# EC25.net
KiCad netlist of a schematic drawn in Altium Designer
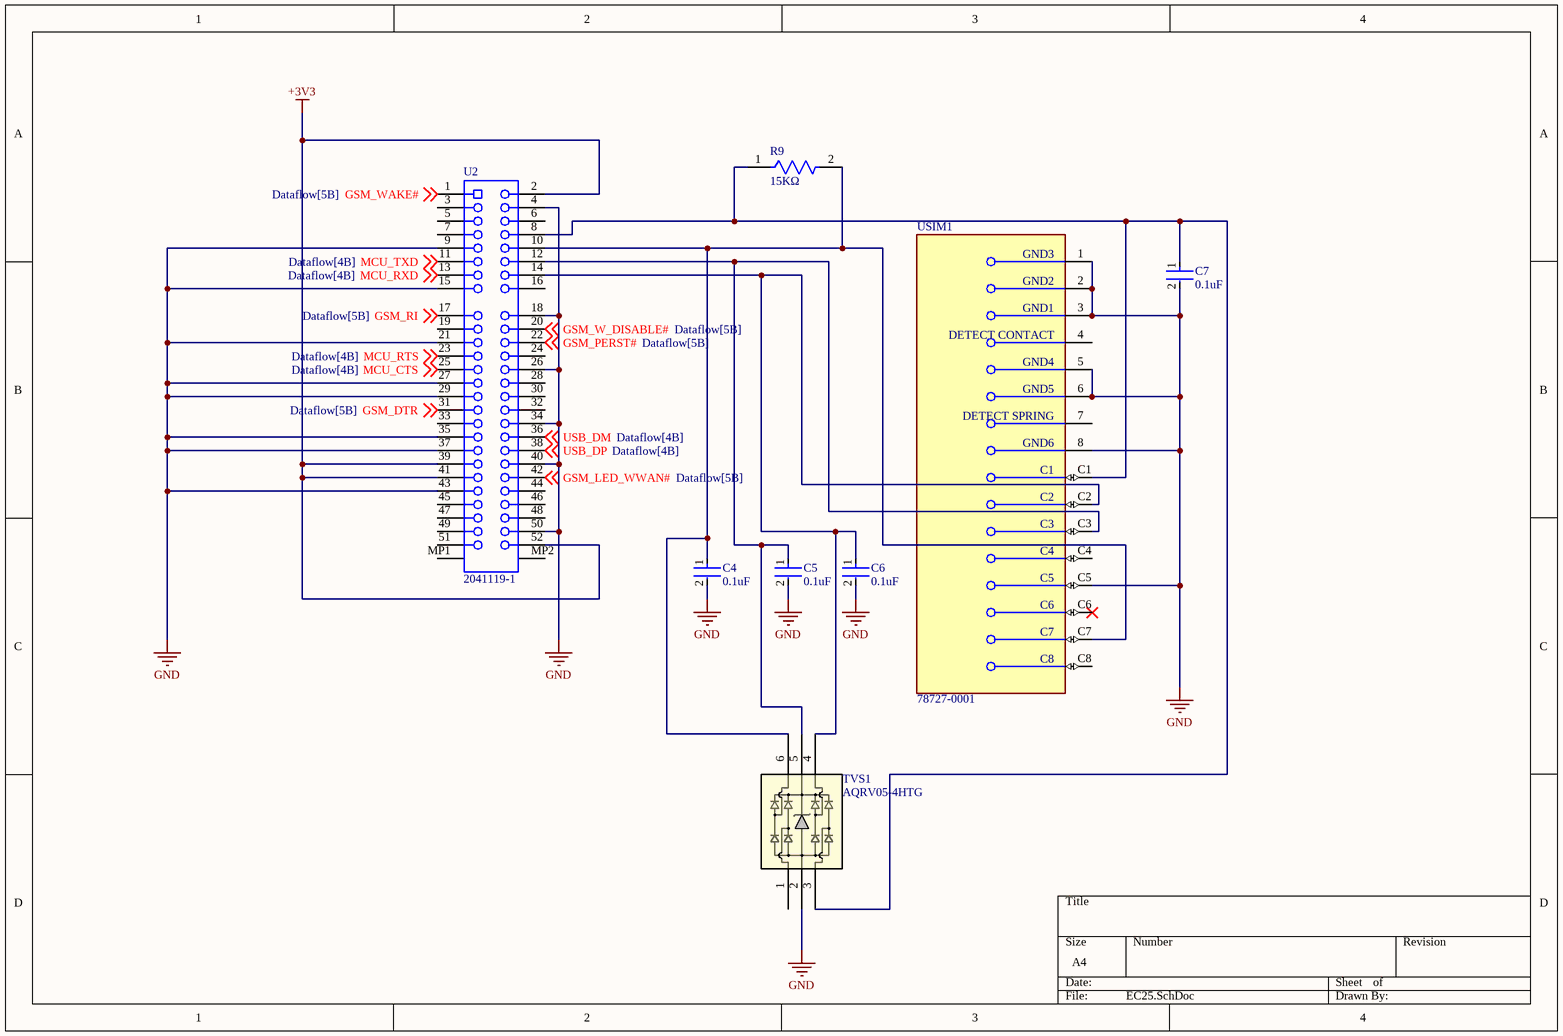
[diagram p0: EC25.SchDoc]

(export (version "E")
  (design (tool "Eeschema 10.0.6"))
  (components
    (comp (ref "C4")
      (value "0.1uF")
      (footprint "FP-C0603C-CF-MFG")
      (description "C0603C104J5RACTU CAP CER 0.1UF 50V 5% X7R 0603")
      (fields (field (name "TOLERANCE") "0.05") (field (name "MANUFACTURER PART NUMBER") "C0603C104J5RACTU"))
      (libsource (lib "Altium Content Vault") (part "b4654b650e69147ec39a6b967a45e02"))
    )
    (comp (ref "C5")
      (value "0.1uF")
      (footprint "FP-C0603C-CF-MFG")
      (description "C0603C104J5RACTU CAP CER 0.1UF 50V 5% X7R 0603")
      (fields (field (name "TOLERANCE") "0.05") (field (name "MANUFACTURER PART NUMBER") "C0603C104J5RACTU"))
      (libsource (lib "Altium Content Vault") (part "b4654b650e69147ec39a6b967a45e02"))
    )
    (comp (ref "C6")
      (value "0.1uF")
      (footprint "FP-C0603C-CF-MFG")
      (description "C0603C104J5RACTU CAP CER 0.1UF 50V 5% X7R 0603")
      (fields (field (name "TOLERANCE") "0.05") (field (name "MANUFACTURER PART NUMBER") "C0603C104J5RACTU"))
      (libsource (lib "Altium Content Vault") (part "b4654b650e69147ec39a6b967a45e02"))
    )
    (comp (ref "C7")
      (value "0.1uF")
      (footprint "FP-C0603C-CF-MFG")
      (description "C0603C104J5RACTU CAP CER 0.1UF 50V 5% X7R 0603")
      (fields (field (name "TOLERANCE") "0.05") (field (name "MANUFACTURER PART NUMBER") "C0603C104J5RACTU"))
      (libsource (lib "Altium Content Vault") (part "b4654b650e69147ec39a6b967a45e02"))
    )
    (comp (ref "R9")
      (value "15KΩ")
      (footprint "FP-CRGP2512-IPC_C")
      (description "CRGP2512F15K CRGP2512 15KΩ 2W ±100ppm/°C 1% 500V")
      (fields (field (name "TOLERANCE") "0.01") (field (name "MANUFACTURER PART NUMBER") "CRGP2512F15K"))
      (libsource (lib "Altium Content Vault") (part "1029c3af85768c4190bb7ad29bc67b5"))
    )
    (comp (ref "TVS1")
      (value "AQRV05-4HTG")
      (footprint "SOT23-6_LTF")
      (description "No Description Available")
      (libsource (lib "AQRV05-4HTG") (part "AQRV05-4HTG"))
    )
    (comp (ref "U2")
      (value "2041119-1")
      (footprint "TECO-2041119-1_3_V")
      (fields (field (name "MANUFACTURER") "TE Connectivity"))
      (libsource (lib "Altium Content Vault") (part "CN-2P-2F-R52"))
    )
    (comp (ref "USIM1")
      (value "78727-0001")
      (footprint "FP-78727-0001-MFG")
      (description "CONN MICRO SIM CARD PUSH-PULL")
      (fields
        (field (name "OCTOPART") "https://octopart.com/78727-0001-molex-24436211")
        (field (name "MANUFACTURER") "Molex")
      )
      (libsource (lib "Altium Content Vault") (part "009f4dc804d36d98447081ee26a76dc"))
    )
  )
  (nets
    (net (code "1") (name "+3V3") (class "Default")
      (node (ref "U2") (pin "2") (pinfunction "2_2") (pintype "passive"))
      (node (ref "U2") (pin "39") (pinfunction "39_39") (pintype "passive"))
      (node (ref "U2") (pin "41") (pinfunction "41_41") (pintype "passive"))
      (node (ref "U2") (pin "52") (pinfunction "52_52") (pintype "passive"))
    )
    (net (code "2") (name "GND") (class "Default")
      (node (ref "C4") (pin "2") (pinfunction "2_2") (pintype "passive"))
      (node (ref "C5") (pin "2") (pinfunction "2_2") (pintype "passive"))
      (node (ref "C6") (pin "2") (pinfunction "2_2") (pintype "passive"))
      (node (ref "C7") (pin "2") (pinfunction "2_2") (pintype "passive"))
      (node (ref "TVS1") (pin "2") (pinfunction "2_2") (pintype "passive"))
      (node (ref "U2") (pin "15") (pinfunction "15_15") (pintype "passive"))
      (node (ref "U2") (pin "18") (pinfunction "18_18") (pintype "passive"))
      (node (ref "U2") (pin "21") (pinfunction "21_21") (pintype "passive"))
      (node (ref "U2") (pin "26") (pinfunction "26_26") (pintype "passive"))
      (node (ref "U2") (pin "27") (pinfunction "27_27") (pintype "passive"))
      (node (ref "U2") (pin "29") (pinfunction "29_29") (pintype "passive"))
      (node (ref "U2") (pin "34") (pinfunction "34_34") (pintype "passive"))
      (node (ref "U2") (pin "35") (pinfunction "35_35") (pintype "passive"))
      (node (ref "U2") (pin "37") (pinfunction "37_37") (pintype "passive"))
      (node (ref "U2") (pin "4") (pinfunction "4_4") (pintype "passive"))
      (node (ref "U2") (pin "40") (pinfunction "40_40") (pintype "passive"))
      (node (ref "U2") (pin "43") (pinfunction "43_43") (pintype "passive"))
      (node (ref "U2") (pin "50") (pinfunction "50_50") (pintype "passive"))
      (node (ref "U2") (pin "9") (pinfunction "9_9") (pintype "passive"))
      (node (ref "USIM1") (pin "1") (pinfunction "GND3_1") (pintype "power_in"))
      (node (ref "USIM1") (pin "2") (pinfunction "GND2_2") (pintype "power_in"))
      (node (ref "USIM1") (pin "3") (pinfunction "GND1_3") (pintype "power_in"))
      (node (ref "USIM1") (pin "5") (pinfunction "GND4_5") (pintype "power_in"))
      (node (ref "USIM1") (pin "6") (pinfunction "GND5_6") (pintype "power_in"))
      (node (ref "USIM1") (pin "8") (pinfunction "GND6_8") (pintype "power_in"))
      (node (ref "USIM1") (pin "C5") (pinfunction "C5_C5") (pintype "bidirectional"))
    )
    (net (code "3") (name "GSM_DTR") (class "Default")
      (node (ref "U2") (pin "31") (pinfunction "31_31") (pintype "passive"))
    )
    (net (code "4") (name "GSM_LED_WWAN#") (class "Default")
      (node (ref "U2") (pin "42") (pinfunction "42_42") (pintype "passive"))
    )
    (net (code "5") (name "GSM_PERST#") (class "Default")
      (node (ref "U2") (pin "22") (pinfunction "22_22") (pintype "passive"))
    )
    (net (code "6") (name "GSM_RI") (class "Default")
      (node (ref "U2") (pin "17") (pinfunction "17_17") (pintype "passive"))
    )
    (net (code "7") (name "GSM_WAKE#") (class "Default")
      (node (ref "U2") (pin "1") (pinfunction "1_1") (pintype "passive"))
    )
    (net (code "8") (name "GSM_W_DISABLE#") (class "Default")
      (node (ref "U2") (pin "20") (pinfunction "20_20") (pintype "passive"))
    )
    (net (code "9") (name "MCU_CTS") (class "Default")
      (node (ref "U2") (pin "25") (pinfunction "25_25") (pintype "passive"))
    )
    (net (code "10") (name "MCU_RTS") (class "Default")
      (node (ref "U2") (pin "23") (pinfunction "23_23") (pintype "passive"))
    )
    (net (code "11") (name "MCU_RXD") (class "Default")
      (node (ref "U2") (pin "13") (pinfunction "13_13") (pintype "passive"))
    )
    (net (code "12") (name "MCU_TXD") (class "Default")
      (node (ref "U2") (pin "11") (pinfunction "11_11") (pintype "passive"))
    )
    (net (code "13") (name "Net-(C4-Pad1)") (class "Default")
      (node (ref "C4") (pin "1") (pinfunction "1_1") (pintype "passive"))
      (node (ref "R9") (pin "2") (pinfunction "2_2") (pintype "passive"))
      (node (ref "TVS1") (pin "6") (pinfunction "6_6") (pintype "passive"))
      (node (ref "U2") (pin "10") (pinfunction "10_10") (pintype "passive"))
      (node (ref "USIM1") (pin "C7") (pinfunction "C7_C7") (pintype "bidirectional"))
    )
    (net (code "14") (name "Net-(C5-Pad1)") (class "Default")
      (node (ref "C5") (pin "1") (pinfunction "1_1") (pintype "passive"))
      (node (ref "TVS1") (pin "5") (pinfunction "5_5") (pintype "passive"))
      (node (ref "U2") (pin "12") (pinfunction "12_12") (pintype "passive"))
      (node (ref "USIM1") (pin "C3") (pinfunction "C3_C3") (pintype "bidirectional"))
    )
    (net (code "15") (name "Net-(C6-Pad1)") (class "Default")
      (node (ref "C6") (pin "1") (pinfunction "1_1") (pintype "passive"))
      (node (ref "TVS1") (pin "4") (pinfunction "4_4") (pintype "passive"))
      (node (ref "U2") (pin "14") (pinfunction "14_14") (pintype "passive"))
      (node (ref "USIM1") (pin "C2") (pinfunction "C2_C2") (pintype "bidirectional"))
    )
    (net (code "16") (name "Net-(C7-Pad1)") (class "Default")
      (node (ref "C7") (pin "1") (pinfunction "1_1") (pintype "passive"))
      (node (ref "R9") (pin "1") (pinfunction "1_1") (pintype "passive"))
      (node (ref "TVS1") (pin "3") (pinfunction "3_3") (pintype "passive"))
      (node (ref "U2") (pin "8") (pinfunction "8_8") (pintype "passive"))
      (node (ref "USIM1") (pin "C1") (pinfunction "C1_C1") (pintype "bidirectional"))
    )
    (net (code "17") (name "USB_DM") (class "Default")
      (node (ref "U2") (pin "36") (pinfunction "36_36") (pintype "passive"))
    )
    (net (code "18") (name "USB_DP") (class "Default")
      (node (ref "U2") (pin "38") (pinfunction "38_38") (pintype "passive"))
    )
    (net (code "19") (name "unconnected-(TVS1-Pad1)") (class "Default")
      (node (ref "TVS1") (pin "1") (pinfunction "1_1") (pintype "passive"))
    )
    (net (code "20") (name "unconnected-(U2-Pad3)") (class "Default")
      (node (ref "U2") (pin "3") (pinfunction "3_3") (pintype "passive"))
    )
    (net (code "21") (name "unconnected-(U2-Pad5)") (class "Default")
      (node (ref "U2") (pin "5") (pinfunction "5_5") (pintype "passive"))
    )
    (net (code "22") (name "unconnected-(U2-Pad6)") (class "Default")
      (node (ref "U2") (pin "6") (pinfunction "6_6") (pintype "passive"))
    )
    (net (code "23") (name "unconnected-(U2-Pad7)") (class "Default")
      (node (ref "U2") (pin "7") (pinfunction "7_7") (pintype "passive"))
    )
    (net (code "24") (name "unconnected-(U2-Pad16)") (class "Default")
      (node (ref "U2") (pin "16") (pinfunction "16_16") (pintype "passive"))
    )
    (net (code "25") (name "unconnected-(U2-Pad19)") (class "Default")
      (node (ref "U2") (pin "19") (pinfunction "19_19") (pintype "passive"))
    )
    (net (code "26") (name "unconnected-(U2-Pad24)") (class "Default")
      (node (ref "U2") (pin "24") (pinfunction "24_24") (pintype "passive"))
    )
    (net (code "27") (name "unconnected-(U2-Pad28)") (class "Default")
      (node (ref "U2") (pin "28") (pinfunction "28_28") (pintype "passive"))
    )
    (net (code "28") (name "unconnected-(U2-Pad30)") (class "Default")
      (node (ref "U2") (pin "30") (pinfunction "30_30") (pintype "passive"))
    )
    (net (code "29") (name "unconnected-(U2-Pad32)") (class "Default")
      (node (ref "U2") (pin "32") (pinfunction "32_32") (pintype "passive"))
    )
    (net (code "30") (name "unconnected-(U2-Pad33)") (class "Default")
      (node (ref "U2") (pin "33") (pinfunction "33_33") (pintype "passive"))
    )
    (net (code "31") (name "unconnected-(U2-Pad44)") (class "Default")
      (node (ref "U2") (pin "44") (pinfunction "44_44") (pintype "passive"))
    )
    (net (code "32") (name "unconnected-(U2-Pad45)") (class "Default")
      (node (ref "U2") (pin "45") (pinfunction "45_45") (pintype "passive"))
    )
    (net (code "33") (name "unconnected-(U2-Pad46)") (class "Default")
      (node (ref "U2") (pin "46") (pinfunction "46_46") (pintype "passive"))
    )
    (net (code "34") (name "unconnected-(U2-Pad47)") (class "Default")
      (node (ref "U2") (pin "47") (pinfunction "47_47") (pintype "passive"))
    )
    (net (code "35") (name "unconnected-(U2-Pad48)") (class "Default")
      (node (ref "U2") (pin "48") (pinfunction "48_48") (pintype "passive"))
    )
    (net (code "36") (name "unconnected-(U2-Pad49)") (class "Default")
      (node (ref "U2") (pin "49") (pinfunction "49_49") (pintype "passive"))
    )
    (net (code "37") (name "unconnected-(U2-Pad51)") (class "Default")
      (node (ref "U2") (pin "51") (pinfunction "51_51") (pintype "passive"))
    )
    (net (code "38") (name "unconnected-(U2-PadMP1)") (class "Default")
      (node (ref "U2") (pin "MP1") (pinfunction "MP1_MP1") (pintype "passive"))
    )
    (net (code "39") (name "unconnected-(U2-PadMP2)") (class "Default")
      (node (ref "U2") (pin "MP2") (pinfunction "MP2_MP2") (pintype "passive"))
    )
    (net (code "40") (name "unconnected-(USIM1-DETECT_CONTACT-Pad4)") (class "Default")
      (node (ref "USIM1") (pin "4") (pinfunction "DETECT_CONTACT_4") (pintype "passive"))
    )
    (net (code "41") (name "unconnected-(USIM1-DETECT_SPRING-Pad7)") (class "Default")
      (node (ref "USIM1") (pin "7") (pinfunction "DETECT_SPRING_7") (pintype "passive"))
    )
    (net (code "42") (name "unconnected-(USIM1-PadC4)") (class "Default")
      (node (ref "USIM1") (pin "C4") (pinfunction "C4_C4") (pintype "bidirectional"))
    )
    (net (code "43") (name "unconnected-(USIM1-PadC6)") (class "Default")
      (node (ref "USIM1") (pin "C6") (pinfunction "C6_C6") (pintype "bidirectional+no_connect"))
    )
    (net (code "44") (name "unconnected-(USIM1-PadC8)") (class "Default")
      (node (ref "USIM1") (pin "C8") (pinfunction "C8_C8") (pintype "bidirectional"))
    )
  )
)
